# Power_Supplies.net
KiCad netlist of a schematic drawn in Altium Designer
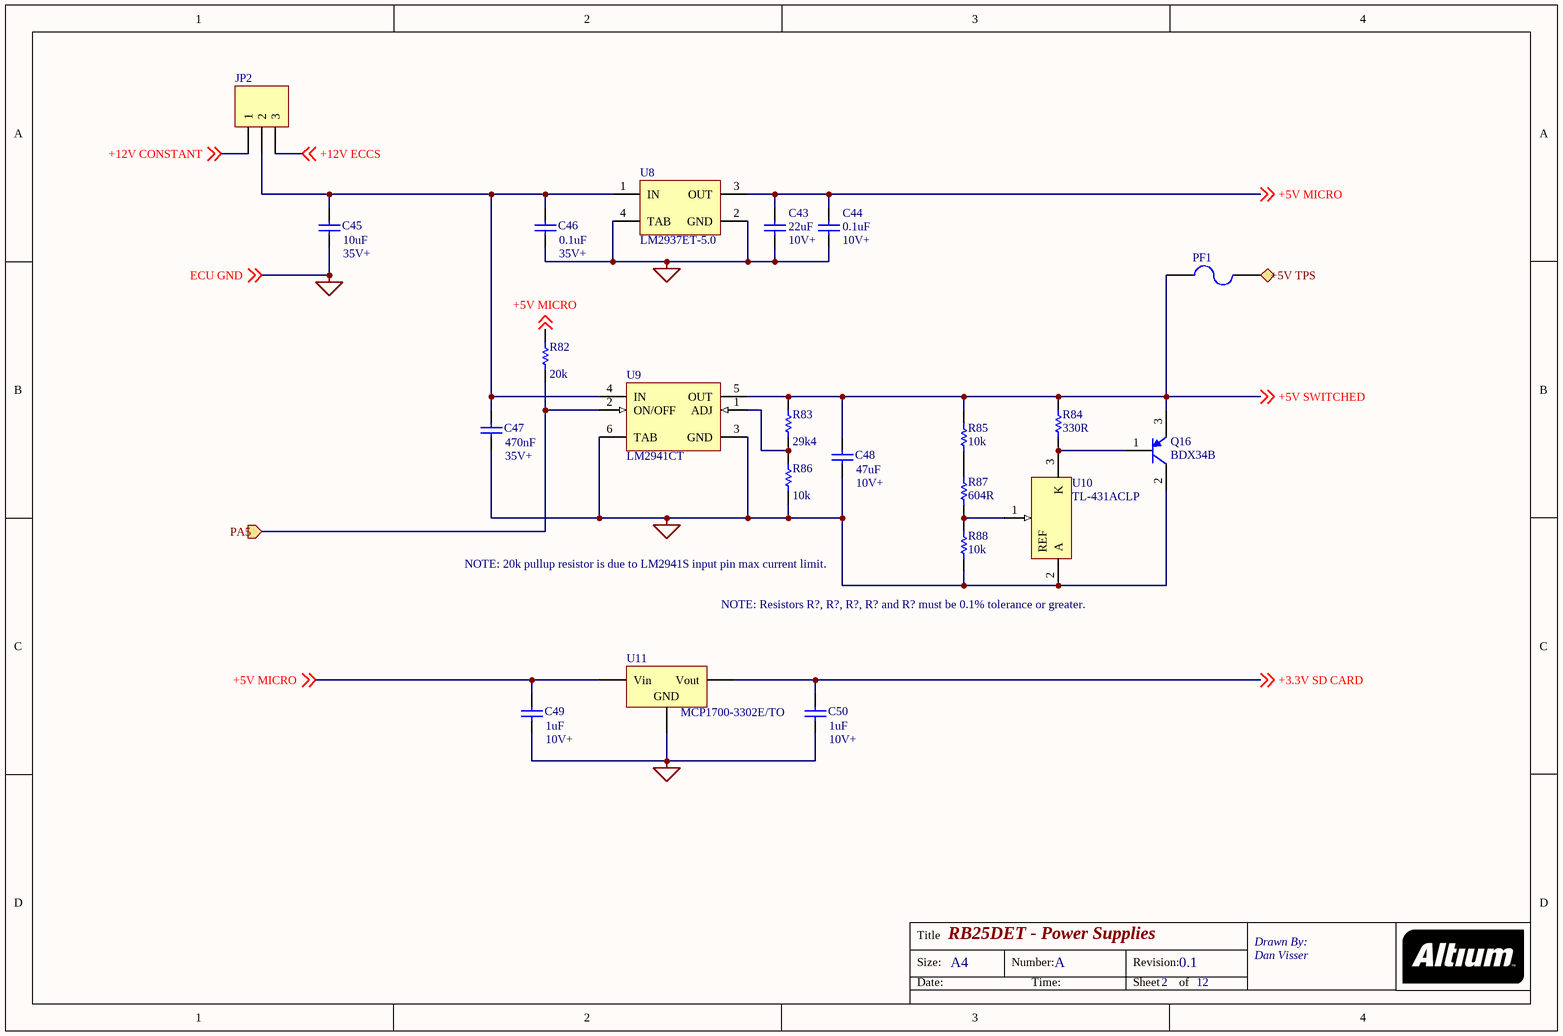
[diagram p0: Power Supplies.SchDoc]

(export (version "E")
  (design (tool "Eeschema 10.0.6"))
  (components
    (comp (ref "C43")
      (value "22uF")
      (footprint "RAD-0.3")
      (description "Capacitor")
      (fields (field (name "PUBLISHER") "Altium Limited"))
      (libsource (lib "Miscellaneous Devices") (part "Cap"))
    )
    (comp (ref "C44")
      (value "0.1uF")
      (footprint "RAD-0.3")
      (description "Capacitor")
      (fields (field (name "PUBLISHER") "Altium Limited"))
      (libsource (lib "Miscellaneous Devices") (part "Cap"))
    )
    (comp (ref "C45")
      (value "10uF")
      (footprint "RAD-0.3")
      (description "Capacitor")
      (fields (field (name "PUBLISHER") "Altium Limited"))
      (libsource (lib "Miscellaneous Devices") (part "Cap"))
    )
    (comp (ref "C46")
      (value "0.1uF")
      (footprint "RAD-0.3")
      (description "Capacitor")
      (fields (field (name "PUBLISHER") "Altium Limited"))
      (libsource (lib "Miscellaneous Devices") (part "Cap"))
    )
    (comp (ref "C47")
      (value "470nF")
      (footprint "RAD-0.3")
      (description "Capacitor")
      (fields (field (name "PUBLISHER") "Altium Limited"))
      (libsource (lib "Miscellaneous Devices") (part "Cap"))
    )
    (comp (ref "C48")
      (value "47uF")
      (footprint "RAD-0.3")
      (description "Capacitor")
      (fields (field (name "PUBLISHER") "Altium Limited"))
      (libsource (lib "Miscellaneous Devices") (part "Cap"))
    )
    (comp (ref "C49")
      (value "1uF")
      (footprint "RAD-0.3")
      (description "Capacitor")
      (fields (field (name "PUBLISHER") "Altium Limited"))
      (libsource (lib "Miscellaneous Devices") (part "Cap"))
    )
    (comp (ref "C50")
      (value "1uF")
      (footprint "RAD-0.3")
      (description "Capacitor")
      (fields (field (name "PUBLISHER") "Altium Limited"))
      (libsource (lib "Miscellaneous Devices") (part "Cap"))
    )
    (comp (ref "JP2")
      (value "~")
      (footprint "HDR1X3")
      (description "Header, 3-Pin")
      (fields (field (name "PUBLISHER") "Altium Limited"))
      (libsource (lib "Miscellaneous Connectors") (part "Header 3"))
    )
    (comp (ref "PF1")
      (value "~")
      (footprint "PIN-W2/E2.8")
      (description "Fuse")
      (fields (field (name "PUBLISHER") "Altium Limited"))
      (libsource (lib "Miscellaneous Devices") (part "Fuse 2"))
    )
    (comp (ref "Q16")
      (value "BDX34B")
      (footprint "SOT-23B_N")
      (description "PNP Bipolar Transistor")
      (fields (field (name "PUBLISHER") "Altium Limited"))
      (libsource (lib "Miscellaneous Devices") (part "PNP"))
    )
    (comp (ref "R82")
      (value "20k")
      (footprint "AXIAL-0.3")
      (description "Resistor")
      (fields (field (name "PUBLISHER") "Altium Limited"))
      (libsource (lib "Miscellaneous Devices") (part "Res1"))
    )
    (comp (ref "R83")
      (value "29k4")
      (footprint "AXIAL-0.3")
      (description "Resistor")
      (fields (field (name "PUBLISHER") "Altium Limited"))
      (libsource (lib "Miscellaneous Devices") (part "Res1"))
    )
    (comp (ref "R84")
      (value "330R")
      (footprint "AXIAL-0.3")
      (description "Resistor")
      (fields (field (name "PUBLISHER") "Altium Limited"))
      (libsource (lib "Miscellaneous Devices") (part "Res1"))
    )
    (comp (ref "R85")
      (value "10k")
      (footprint "AXIAL-0.3")
      (description "Resistor")
      (fields (field (name "PUBLISHER") "Altium Limited"))
      (libsource (lib "Miscellaneous Devices") (part "Res1"))
    )
    (comp (ref "R86")
      (value "10k")
      (footprint "AXIAL-0.3")
      (description "Resistor")
      (fields (field (name "PUBLISHER") "Altium Limited"))
      (libsource (lib "Miscellaneous Devices") (part "Res1"))
    )
    (comp (ref "R87")
      (value "604R")
      (footprint "AXIAL-0.3")
      (description "Resistor")
      (fields (field (name "PUBLISHER") "Altium Limited"))
      (libsource (lib "Miscellaneous Devices") (part "Res1"))
    )
    (comp (ref "R88")
      (value "10k")
      (footprint "AXIAL-0.3")
      (description "Resistor")
      (fields (field (name "PUBLISHER") "Altium Limited"))
      (libsource (lib "Miscellaneous Devices") (part "Res1"))
    )
    (comp (ref "U8")
      (value "LM2937ET-5.0")
      (footprint "TS3B_N")
      (description "500 mA Low Dropout Regulator, 3-pin TO-263")
      (fields
        (field (name "PARTNUMBER") "LM2937ES-5.0")
        (field (name "MANUFACTURER") "National Semiconductor")
        (field (name "PUBLISHER") "Altium Limited")
      )
      (libsource (lib "NSC LDO") (part "LM2937ES-5.0"))
    )
    (comp (ref "U9")
      (value "LM2941CT")
      (footprint "TS5B_N")
      (description "1A Low Dropout Adjustable Regulator, 5-pin TO-263")
      (fields
        (field (name "PARTNUMBER") "LM2941S")
        (field (name "MANUFACTURER") "National Semiconductor")
        (field (name "PUBLISHER") "Altium Limited")
      )
      (libsource (lib "NSC LDO") (part "LM2941S"))
    )
    (comp (ref "U10") (value "TL-431ACLP") (libsource (lib "PM-REF-431-SIL3") (part "PM-REF-431-SIL3")))
    (comp (ref "U11")
      (value "MCP1700-3302E/TO")
      (footprint "SOT-23-NB3_M")
      (description "Voltage Regulator")
      (fields (field (name "PUBLISHER") "Altium Limited"))
      (libsource (lib "Miscellaneous Devices") (part "Volt Reg"))
    )
  )
  (nets
    (net (code "1") (name "+3.3V SD CARD") (class "Default")
      (node (ref "C50") (pin "2") (pinfunction "2_2") (pintype "passive"))
      (node (ref "U11") (pin "3") (pinfunction "Vout_3") (pintype "passive"))
    )
    (net (code "2") (name "+5V MICRO") (class "Default")
      (node (ref "C43") (pin "2") (pinfunction "2_2") (pintype "passive"))
      (node (ref "C44") (pin "2") (pinfunction "2_2") (pintype "passive"))
      (node (ref "C49") (pin "2") (pinfunction "2_2") (pintype "passive"))
      (node (ref "R82") (pin "2") (pinfunction "2_2") (pintype "passive"))
      (node (ref "U11") (pin "2") (pinfunction "Vin_2") (pintype "passive"))
      (node (ref "U8") (pin "3") (pinfunction "OUT_3") (pintype "power_in"))
    )
    (net (code "3") (name "+5V SWITCHED") (class "Default")
      (node (ref "C48") (pin "2") (pinfunction "2_2") (pintype "passive"))
      (node (ref "PF1") (pin "1") (pinfunction "1_1") (pintype "passive"))
      (node (ref "Q16") (pin "3") (pinfunction "E_3") (pintype "passive"))
      (node (ref "R83") (pin "2") (pinfunction "2_2") (pintype "passive"))
      (node (ref "R84") (pin "2") (pinfunction "2_2") (pintype "passive"))
      (node (ref "R85") (pin "2") (pinfunction "2_2") (pintype "passive"))
      (node (ref "U9") (pin "5") (pinfunction "OUT_5") (pintype "power_in"))
    )
    (net (code "4") (name "+12V CONSTANT") (class "Default")
      (node (ref "JP2") (pin "1") (pinfunction "1_1") (pintype "passive"))
    )
    (net (code "5") (name "+12V ECCS") (class "Default")
      (node (ref "JP2") (pin "3") (pinfunction "3_3") (pintype "passive"))
    )
    (net (code "6") (name "/+5V TPS") (class "Default")
      (node (ref "PF1") (pin "2") (pinfunction "2_2") (pintype "passive"))
    )
    (net (code "7") (name "/PA5") (class "Default")
      (node (ref "R82") (pin "1") (pinfunction "1_1") (pintype "passive"))
      (node (ref "U9") (pin "2") (pinfunction "ON/OFF_2") (pintype "input"))
    )
    (net (code "8") (name "<NO NET>") (class "Default")
      (node (ref "C43") (pin "1") (pinfunction "1_1") (pintype "passive"))
      (node (ref "C44") (pin "1") (pinfunction "1_1") (pintype "passive"))
      (node (ref "C45") (pin "1") (pinfunction "1_1") (pintype "passive"))
      (node (ref "C46") (pin "1") (pinfunction "1_1") (pintype "passive"))
      (node (ref "C47") (pin "1") (pinfunction "1_1") (pintype "passive"))
      (node (ref "C48") (pin "1") (pinfunction "1_1") (pintype "passive"))
      (node (ref "C49") (pin "1") (pinfunction "1_1") (pintype "passive"))
      (node (ref "C50") (pin "1") (pinfunction "1_1") (pintype "passive"))
      (node (ref "Q16") (pin "2") (pinfunction "C_2") (pintype "passive"))
      (node (ref "R86") (pin "1") (pinfunction "1_1") (pintype "passive"))
      (node (ref "R88") (pin "1") (pinfunction "1_1") (pintype "passive"))
      (node (ref "U10") (pin "2") (pinfunction "A_2") (pintype "passive"))
      (node (ref "U11") (pin "1") (pintype "passive"))
      (node (ref "U8") (pin "2") (pinfunction "GND_2") (pintype "power_in"))
      (node (ref "U8") (pin "4") (pinfunction "TAB_4") (pintype "power_in"))
      (node (ref "U9") (pin "3") (pinfunction "GND_3") (pintype "power_in"))
      (node (ref "U9") (pin "6") (pinfunction "TAB_6") (pintype "power_in"))
    )
    (net (code "9") (name "Net-(Q16-B)") (class "Default")
      (node (ref "Q16") (pin "1") (pinfunction "B_1") (pintype "passive"))
      (node (ref "R84") (pin "1") (pinfunction "1_1") (pintype "passive"))
      (node (ref "U10") (pin "3") (pinfunction "K_3") (pintype "passive"))
    )
    (net (code "10") (name "Net-(R85-Pad1)") (class "Default")
      (node (ref "R85") (pin "1") (pinfunction "1_1") (pintype "passive"))
      (node (ref "R87") (pin "2") (pinfunction "2_2") (pintype "passive"))
    )
    (net (code "11") (name "Net-(U8-IN)") (class "Default")
      (node (ref "C45") (pin "2") (pinfunction "2_2") (pintype "passive"))
      (node (ref "C46") (pin "2") (pinfunction "2_2") (pintype "passive"))
      (node (ref "C47") (pin "2") (pinfunction "2_2") (pintype "passive"))
      (node (ref "JP2") (pin "2") (pinfunction "2_2") (pintype "passive"))
      (node (ref "U8") (pin "1") (pinfunction "IN_1") (pintype "power_in"))
      (node (ref "U9") (pin "4") (pinfunction "IN_4") (pintype "power_in"))
    )
    (net (code "12") (name "Net-(U9-ADJ)") (class "Default")
      (node (ref "R83") (pin "1") (pinfunction "1_1") (pintype "passive"))
      (node (ref "R86") (pin "2") (pinfunction "2_2") (pintype "passive"))
      (node (ref "U9") (pin "1") (pinfunction "ADJ_1") (pintype "input"))
    )
    (net (code "13") (name "Net-(U10-REF)") (class "Default")
      (node (ref "R87") (pin "1") (pinfunction "1_1") (pintype "passive"))
      (node (ref "R88") (pin "2") (pinfunction "2_2") (pintype "passive"))
      (node (ref "U10") (pin "1") (pinfunction "REF_1") (pintype "input"))
    )
  )
)
